# BoB_Brain_v03.net
KiCad netlist of a schematic drawn in EAGLE
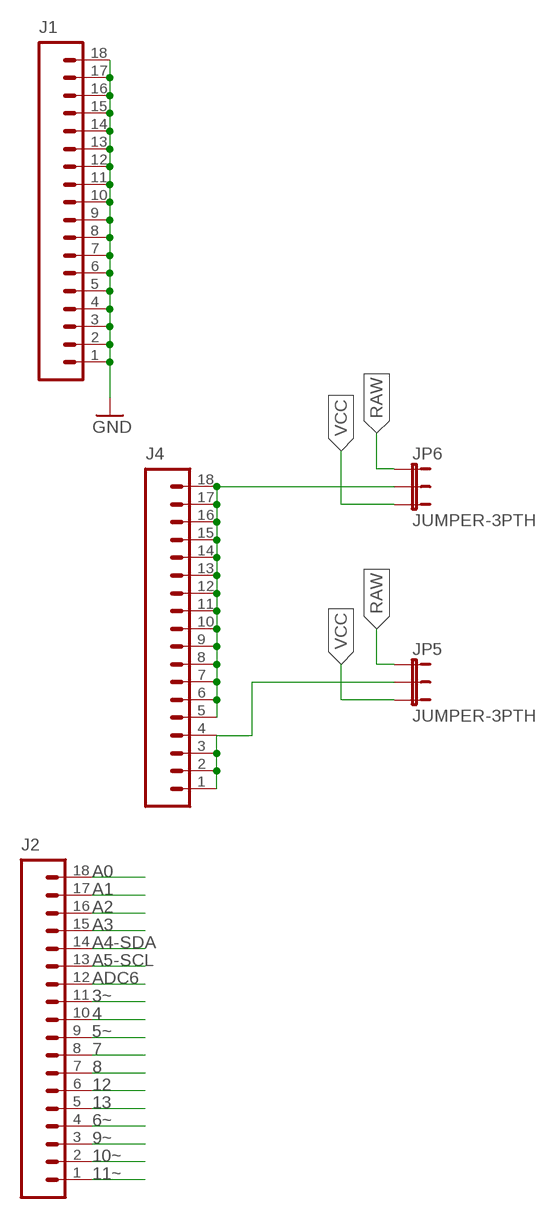
[diagram p0: schematic, sheet 1]
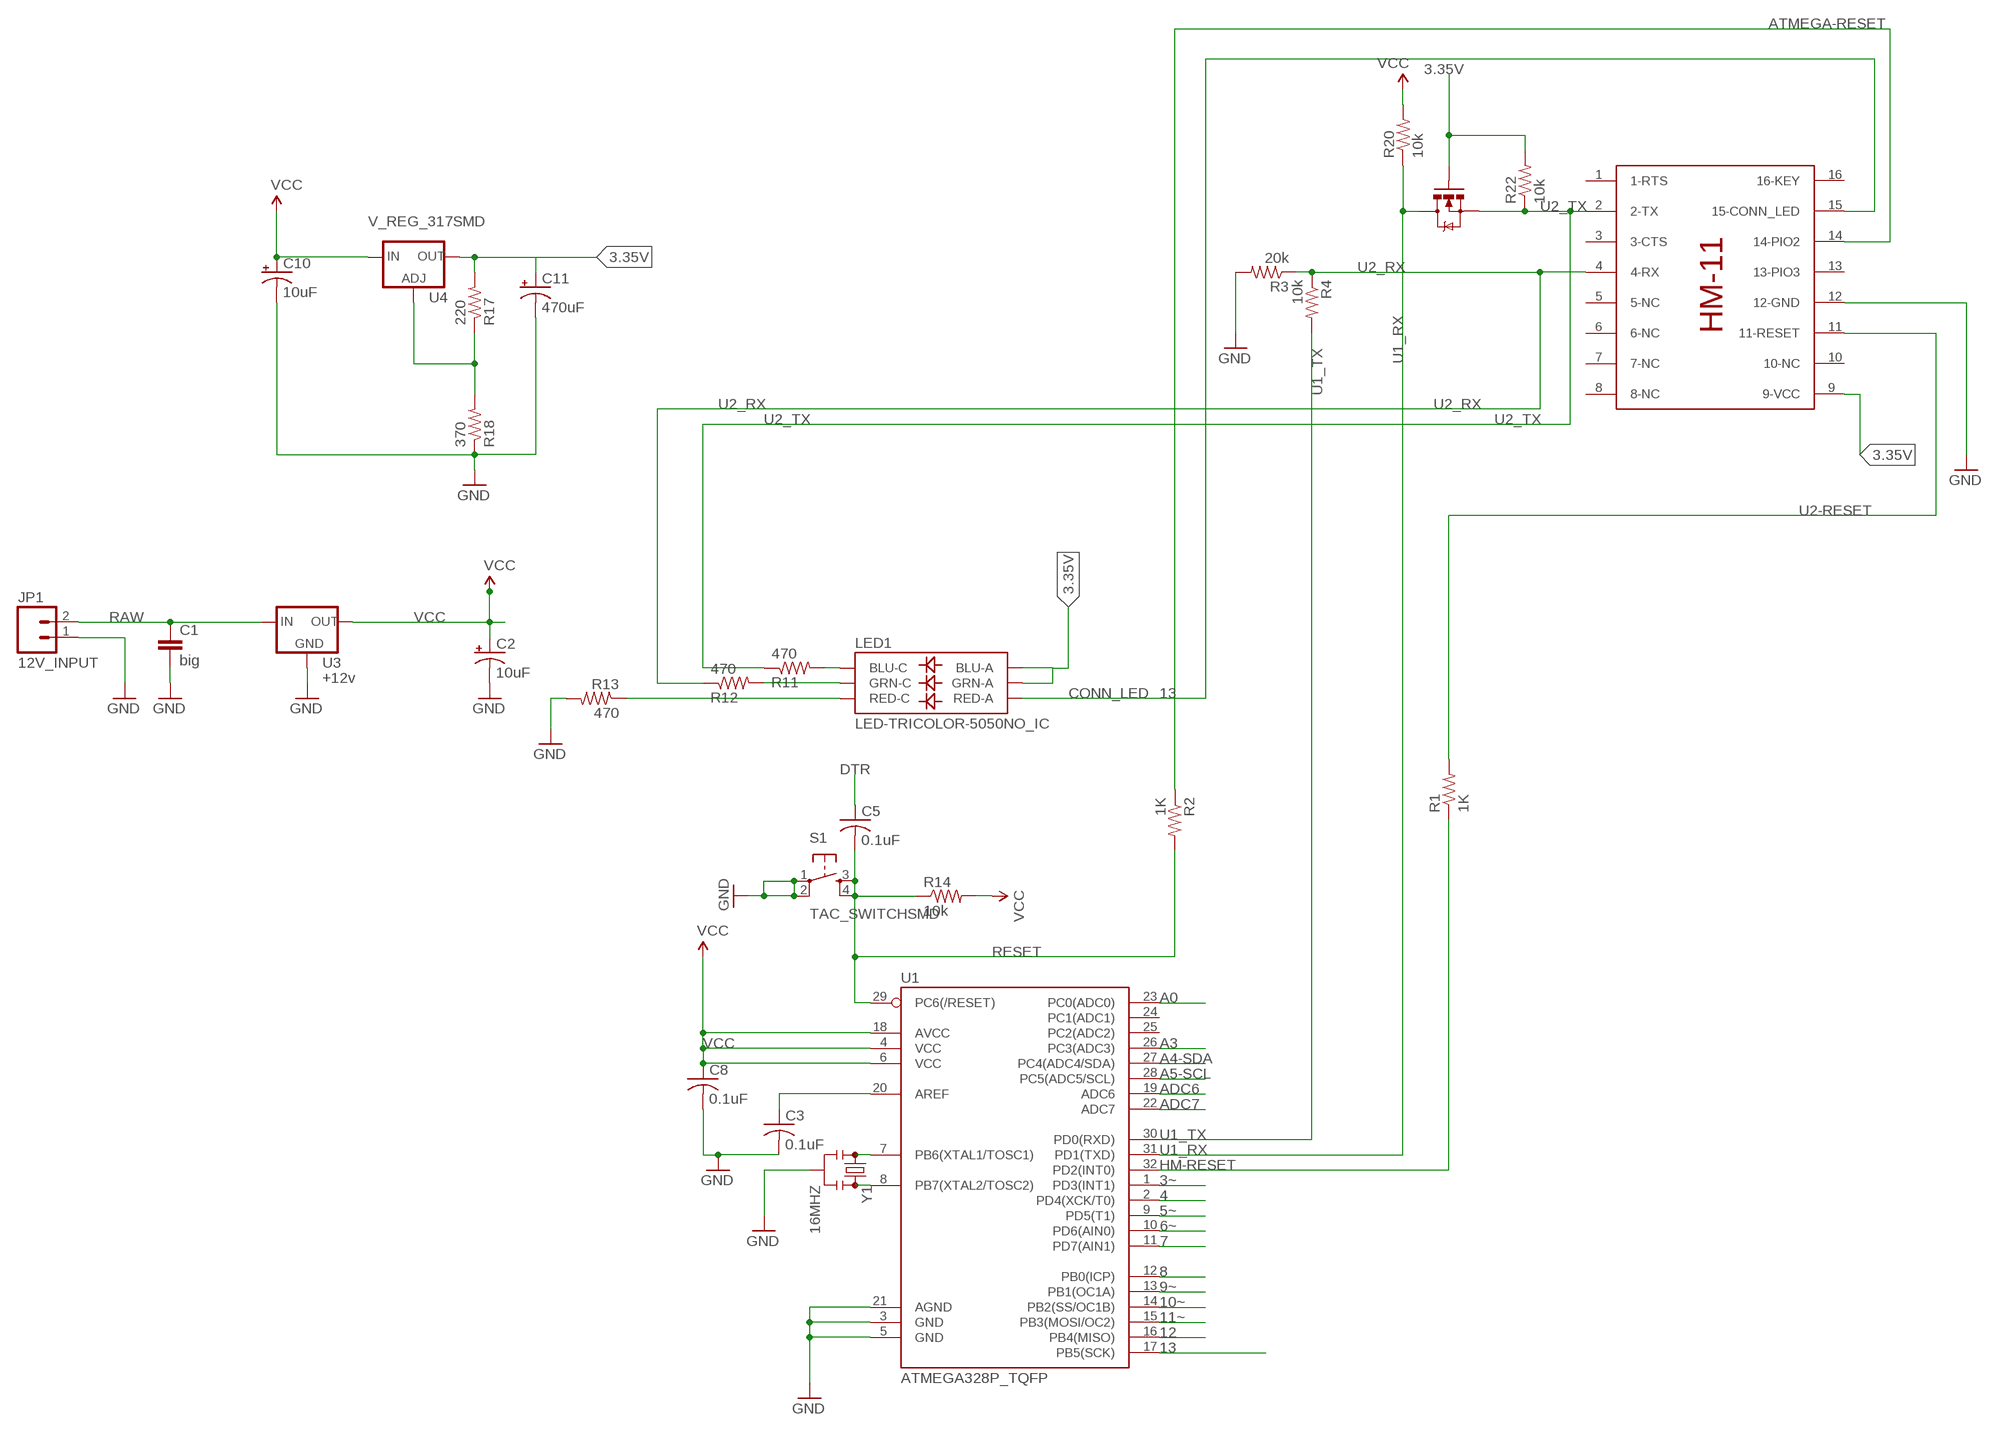
[diagram p1: schematic, sheet 2]

(export (version "E")
  (design (tool "Eeschema 10.0.6"))
  (components
    (comp (ref "C1")
      (value "big")
      (footprint "eagle-import:CAP-PTH-5MM")
      (libsource (lib "eagle-import") (part "CAPPTH1"))
    )
    (comp (ref "C2")
      (value "10uF")
      (footprint "eagle-import:EIA3528")
      (libsource (lib "eagle-import") (part "CAP_POL3528"))
    )
    (comp (ref "C3")
      (value "0.1uF")
      (footprint "eagle-import:C0402")
      (libsource (lib "eagle-import") (part "C-USC0402"))
    )
    (comp (ref "C5")
      (value "0.1uF")
      (footprint "eagle-import:C0805K")
      (libsource (lib "eagle-import") (part "C-USC0805K"))
    )
    (comp (ref "C8")
      (value "0.1uF")
      (footprint "eagle-import:C0402")
      (libsource (lib "eagle-import") (part "C-USC0402"))
    )
    (comp (ref "C10")
      (value "10uF")
      (footprint "eagle-import:EIA3528")
      (libsource (lib "eagle-import") (part "CAP_POL3528"))
    )
    (comp (ref "C11")
      (value "470uF")
      (footprint "eagle-import:D_7343-31W")
      (libsource (lib "eagle-import") (part "CPOL-USD/7343-31W"))
    )
    (comp (ref "JP1")
      (value "12V_INPUT")
      (footprint "eagle-import:SCREWTERMINAL-5MM-2")
      (libsource (lib "eagle-import") (part "M025MM"))
    )
    (comp (ref "LED1")
      (value "LED-TRICOLOR-5050NO_IC")
      (footprint "eagle-import:LED-TRICOLOR-5050")
      (libsource (lib "eagle-import") (part "LED-TRICOLOR-5050NO_IC"))
    )
    (comp (ref "Q1")
      (value "MOSFET-NCHANNELAO3404A")
      (footprint "eagle-import:SOT23-3")
      (libsource (lib "eagle-import") (part "MOSFET-NCHANNELAO3404A"))
    )
    (comp (ref "R1")
      (value "1K")
      (footprint "eagle-import:R0805W")
      (libsource (lib "eagle-import") (part "R-US_R0805W"))
    )
    (comp (ref "R2")
      (value "1K")
      (footprint "eagle-import:R0805W")
      (libsource (lib "eagle-import") (part "R-US_R0805W"))
    )
    (comp (ref "R3")
      (value "20k")
      (footprint "eagle-import:R0805W")
      (libsource (lib "eagle-import") (part "R-US_R0805W"))
    )
    (comp (ref "R4")
      (value "10k")
      (footprint "eagle-import:R0805W")
      (libsource (lib "eagle-import") (part "R-US_R0805W"))
    )
    (comp (ref "R11")
      (value "470")
      (footprint "eagle-import:R0805W")
      (libsource (lib "eagle-import") (part "R-US_R0805W"))
    )
    (comp (ref "R12")
      (value "470")
      (footprint "eagle-import:R0805W")
      (libsource (lib "eagle-import") (part "R-US_R0805W"))
    )
    (comp (ref "R13")
      (value "470")
      (footprint "eagle-import:R0805W")
      (libsource (lib "eagle-import") (part "R-US_R0805W"))
    )
    (comp (ref "R14")
      (value "10k")
      (footprint "eagle-import:R0805W")
      (libsource (lib "eagle-import") (part "R-US_R0805W"))
    )
    (comp (ref "R17")
      (value "220")
      (footprint "eagle-import:R0805W")
      (libsource (lib "eagle-import") (part "R-US_R0805W"))
    )
    (comp (ref "R18")
      (value "370")
      (footprint "eagle-import:R0805W")
      (libsource (lib "eagle-import") (part "R-US_R0805W"))
    )
    (comp (ref "R20")
      (value "10k")
      (footprint "eagle-import:R0805W")
      (libsource (lib "eagle-import") (part "R-US_R0805W"))
    )
    (comp (ref "R22")
      (value "10k")
      (footprint "eagle-import:R0805W")
      (libsource (lib "eagle-import") (part "R-US_R0805W"))
    )
    (comp (ref "S1")
      (value "TAC_SWITCHSMD")
      (footprint "eagle-import:TACTILE-SWITCH-SMD")
      (libsource (lib "eagle-import") (part "TAC_SWITCHSMD"))
    )
    (comp (ref "U$1")
      (value "HM-11")
      (footprint "eagle-import:HM-11")
      (libsource (lib "eagle-import") (part "HM-11"))
    )
    (comp (ref "U1")
      (value "ATMEGA328P_TQFP")
      (footprint "eagle-import:TQFP32-08")
      (libsource (lib "eagle-import") (part "ATMEGA328P_TQFP"))
    )
    (comp (ref "U3")
      (value "+12v")
      (footprint "eagle-import:TO-252")
      (libsource (lib "eagle-import") (part "V_REG_78XX7812"))
    )
    (comp (ref "U4")
      (value "V_REG_317SMD")
      (footprint "eagle-import:SOT223")
      (libsource (lib "eagle-import") (part "V_REG_317SMD"))
    )
    (comp (ref "Y1")
      (value "16MHZ")
      (footprint "eagle-import:RESONATOR-SMD")
      (libsource (lib "eagle-import") (part "RESONATOR16MHZ"))
    )
    (comp (ref "J1")
      (value "M18_")
      (footprint "eagle-import:1X18")
      (libsource (lib "eagle-import") (part "M18_"))
    )
    (comp (ref "J2")
      (value "M18_")
      (footprint "eagle-import:1X18")
      (libsource (lib "eagle-import") (part "M18_"))
    )
    (comp (ref "J4")
      (value "M18_")
      (footprint "eagle-import:1X18")
      (libsource (lib "eagle-import") (part "M18_"))
    )
    (comp (ref "JP5")
      (value "JUMPER-3PTH")
      (footprint "eagle-import:1X03")
      (libsource (lib "eagle-import") (part "JUMPER-3PTH"))
    )
    (comp (ref "JP6")
      (value "JUMPER-3PTH")
      (footprint "eagle-import:1X03")
      (libsource (lib "eagle-import") (part "JUMPER-3PTH"))
    )
  )
  (nets
    (net (code "1") (name "3.35V") (class "Default")
      (node (ref "C11") (pin "+") (pinfunction "+_+") (pintype "passive"))
      (node (ref "LED1") (pin "1") (pinfunction "GRN-A_1") (pintype "bidirectional"))
      (node (ref "LED1") (pin "3") (pinfunction "BLU-A_3") (pintype "bidirectional"))
      (node (ref "Q1") (pin "1") (pinfunction "G_1") (pintype "passive"))
      (node (ref "R17") (pin "2") (pinfunction "2_2") (pintype "passive"))
      (node (ref "R22") (pin "2") (pinfunction "2_2") (pintype "passive"))
      (node (ref "U$1") (pin "9") (pinfunction "9-VCC_9") (pintype "bidirectional"))
      (node (ref "U4") (pin "2") (pinfunction "OUT_2") (pintype "output"))
    )
    (net (code "2") (name "3~{}") (class "Default")
      (node (ref "J2") (pin "18") (pinfunction "18_18") (pintype "passive"))
      (node (ref "U1") (pin "1") (pinfunction "PD3(INT1)_1") (pintype "bidirectional"))
    )
    (net (code "3") (name "4") (class "Default")
      (node (ref "J2") (pin "17") (pinfunction "17_17") (pintype "passive"))
      (node (ref "U1") (pin "2") (pinfunction "PD4(XCK/T0)_2") (pintype "bidirectional"))
    )
    (net (code "4") (name "5~{}") (class "Default")
      (node (ref "J2") (pin "9") (pinfunction "9_9") (pintype "passive"))
      (node (ref "U1") (pin "9") (pinfunction "PD5(T1)_9") (pintype "bidirectional"))
    )
    (net (code "5") (name "6~{}") (class "Default")
      (node (ref "J2") (pin "4") (pinfunction "4_4") (pintype "passive"))
      (node (ref "U1") (pin "10") (pinfunction "PD6(AIN0)_10") (pintype "bidirectional"))
    )
    (net (code "6") (name "7") (class "Default")
      (node (ref "J2") (pin "8") (pinfunction "8_8") (pintype "passive"))
      (node (ref "U1") (pin "11") (pinfunction "PD7(AIN1)_11") (pintype "bidirectional"))
    )
    (net (code "7") (name "8") (class "Default")
      (node (ref "J2") (pin "7") (pinfunction "7_7") (pintype "passive"))
      (node (ref "U1") (pin "12") (pinfunction "PB0(ICP)_12") (pintype "bidirectional"))
    )
    (net (code "8") (name "9~{}") (class "Default")
      (node (ref "J2") (pin "3") (pinfunction "3_3") (pintype "passive"))
      (node (ref "U1") (pin "13") (pinfunction "PB1(OC1A)_13") (pintype "bidirectional"))
    )
    (net (code "9") (name "10~{}") (class "Default")
      (node (ref "J2") (pin "2") (pinfunction "2_2") (pintype "passive"))
      (node (ref "U1") (pin "14") (pinfunction "PB2(SS/OC1B)_14") (pintype "bidirectional"))
    )
    (net (code "10") (name "11~{}") (class "Default")
      (node (ref "J2") (pin "1") (pinfunction "1_1") (pintype "passive"))
      (node (ref "U1") (pin "15") (pinfunction "PB3(MOSI/OC2)_15") (pintype "bidirectional"))
    )
    (net (code "11") (name "12") (class "Default")
      (node (ref "J2") (pin "6") (pinfunction "6_6") (pintype "passive"))
      (node (ref "U1") (pin "16") (pinfunction "PB4(MISO)_16") (pintype "bidirectional"))
    )
    (net (code "12") (name "13") (class "Default")
      (node (ref "J2") (pin "5") (pinfunction "5_5") (pintype "passive"))
      (node (ref "U1") (pin "17") (pinfunction "PB5(SCK)_17") (pintype "bidirectional"))
    )
    (net (code "13") (name "A0") (class "Default")
      (node (ref "J2") (pin "12") (pinfunction "12_12") (pintype "passive"))
      (node (ref "U1") (pin "23") (pinfunction "PC0(ADC0)_23") (pintype "bidirectional"))
    )
    (net (code "14") (name "A1") (class "Default")
      (node (ref "J2") (pin "10") (pinfunction "10_10") (pintype "passive"))
    )
    (net (code "15") (name "A2") (class "Default")
      (node (ref "J2") (pin "16") (pinfunction "16_16") (pintype "passive"))
    )
    (net (code "16") (name "A3") (class "Default")
      (node (ref "J2") (pin "15") (pinfunction "15_15") (pintype "passive"))
      (node (ref "U1") (pin "26") (pinfunction "PC3(ADC3)_26") (pintype "bidirectional"))
    )
    (net (code "17") (name "A4-SDA") (class "Default")
      (node (ref "J2") (pin "14") (pinfunction "14_14") (pintype "passive"))
      (node (ref "U1") (pin "27") (pinfunction "PC4(ADC4/SDA)_27") (pintype "bidirectional"))
    )
    (net (code "18") (name "A5-SCL") (class "Default")
      (node (ref "J2") (pin "13") (pinfunction "13_13") (pintype "passive"))
      (node (ref "U1") (pin "28") (pinfunction "PC5(ADC5/SCL)_28") (pintype "bidirectional"))
    )
    (net (code "19") (name "ADC6") (class "Default")
      (node (ref "J2") (pin "11") (pinfunction "11_11") (pintype "passive"))
      (node (ref "U1") (pin "19") (pinfunction "ADC6_19") (pintype "bidirectional"))
    )
    (net (code "20") (name "ADC7") (class "Default")
      (node (ref "U1") (pin "22") (pinfunction "ADC7_22") (pintype "bidirectional"))
    )
    (net (code "21") (name "ATMEGA-RESET") (class "Default")
      (node (ref "R2") (pin "1") (pinfunction "1_1") (pintype "passive"))
      (node (ref "U$1") (pin "14") (pinfunction "14-PIO2_14") (pintype "bidirectional"))
    )
    (net (code "22") (name "CONN_LED") (class "Default")
      (node (ref "LED1") (pin "2") (pinfunction "RED-A_2") (pintype "bidirectional"))
      (node (ref "U$1") (pin "15") (pinfunction "15-CONN_LED_15") (pintype "bidirectional"))
    )
    (net (code "23") (name "DTR") (class "Default")
      (node (ref "C5") (pin "1") (pinfunction "1_1") (pintype "passive"))
    )
    (net (code "24") (name "GND") (class "Default")
      (node (ref "C1") (pin "2") (pinfunction "2_2") (pintype "passive"))
      (node (ref "C10") (pin "C") (pinfunction "-_C") (pintype "passive"))
      (node (ref "C11") (pin "-") (pinfunction "-_-") (pintype "passive"))
      (node (ref "C2") (pin "C") (pinfunction "-_C") (pintype "passive"))
      (node (ref "C3") (pin "2") (pinfunction "2_2") (pintype "passive"))
      (node (ref "C8") (pin "2") (pinfunction "2_2") (pintype "passive"))
      (node (ref "J1") (pin "1") (pinfunction "1_1") (pintype "passive"))
      (node (ref "J1") (pin "10") (pinfunction "10_10") (pintype "passive"))
      (node (ref "J1") (pin "11") (pinfunction "11_11") (pintype "passive"))
      (node (ref "J1") (pin "12") (pinfunction "12_12") (pintype "passive"))
      (node (ref "J1") (pin "13") (pinfunction "13_13") (pintype "passive"))
      (node (ref "J1") (pin "14") (pinfunction "14_14") (pintype "passive"))
      (node (ref "J1") (pin "15") (pinfunction "15_15") (pintype "passive"))
      (node (ref "J1") (pin "16") (pinfunction "16_16") (pintype "passive"))
      (node (ref "J1") (pin "17") (pinfunction "17_17") (pintype "passive"))
      (node (ref "J1") (pin "18") (pinfunction "18_18") (pintype "passive"))
      (node (ref "J1") (pin "2") (pinfunction "2_2") (pintype "passive"))
      (node (ref "J1") (pin "3") (pinfunction "3_3") (pintype "passive"))
      (node (ref "J1") (pin "4") (pinfunction "4_4") (pintype "passive"))
      (node (ref "J1") (pin "5") (pinfunction "5_5") (pintype "passive"))
      (node (ref "J1") (pin "6") (pinfunction "6_6") (pintype "passive"))
      (node (ref "J1") (pin "7") (pinfunction "7_7") (pintype "passive"))
      (node (ref "J1") (pin "8") (pinfunction "8_8") (pintype "passive"))
      (node (ref "J1") (pin "9") (pinfunction "9_9") (pintype "passive"))
      (node (ref "JP1") (pin "1") (pinfunction "1_1") (pintype "passive"))
      (node (ref "R13") (pin "2") (pinfunction "2_2") (pintype "passive"))
      (node (ref "R18") (pin "1") (pinfunction "1_1") (pintype "passive"))
      (node (ref "R3") (pin "2") (pinfunction "2_2") (pintype "passive"))
      (node (ref "S1") (pin "1") (pinfunction "1_1") (pintype "passive"))
      (node (ref "S1") (pin "2") (pinfunction "2_2") (pintype "passive"))
      (node (ref "U$1") (pin "12") (pinfunction "12-GND_12") (pintype "bidirectional"))
      (node (ref "U1") (pin "21") (pinfunction "AGND_21") (pintype "bidirectional"))
      (node (ref "U1") (pin "3") (pinfunction "GND_3") (pintype "bidirectional"))
      (node (ref "U1") (pin "5") (pinfunction "GND_5") (pintype "bidirectional"))
      (node (ref "U3") (pin "3") (pinfunction "GND_3") (pintype "input"))
      (node (ref "Y1") (pin "2") (pinfunction "2_2") (pintype "passive"))
    )
    (net (code "25") (name "HM-RESET") (class "Default")
      (node (ref "R1") (pin "1") (pinfunction "1_1") (pintype "passive"))
      (node (ref "U1") (pin "32") (pinfunction "PD2(INT0)_32") (pintype "bidirectional"))
    )
    (net (code "26") (name "Net-(J4-Pad1)") (class "Default")
      (node (ref "J4") (pin "1") (pinfunction "1_1") (pintype "passive"))
      (node (ref "J4") (pin "2") (pinfunction "2_2") (pintype "passive"))
      (node (ref "J4") (pin "3") (pinfunction "3_3") (pintype "passive"))
      (node (ref "J4") (pin "4") (pinfunction "4_4") (pintype "passive"))
      (node (ref "JP5") (pin "2") (pinfunction "2_2") (pintype "passive"))
    )
    (net (code "27") (name "Net-(J4-Pad10)") (class "Default")
      (node (ref "J4") (pin "10") (pinfunction "10_10") (pintype "passive"))
      (node (ref "J4") (pin "11") (pinfunction "11_11") (pintype "passive"))
      (node (ref "J4") (pin "12") (pinfunction "12_12") (pintype "passive"))
      (node (ref "J4") (pin "13") (pinfunction "13_13") (pintype "passive"))
      (node (ref "J4") (pin "14") (pinfunction "14_14") (pintype "passive"))
      (node (ref "J4") (pin "15") (pinfunction "15_15") (pintype "passive"))
      (node (ref "J4") (pin "16") (pinfunction "16_16") (pintype "passive"))
      (node (ref "J4") (pin "17") (pinfunction "17_17") (pintype "passive"))
      (node (ref "J4") (pin "18") (pinfunction "18_18") (pintype "passive"))
      (node (ref "J4") (pin "5") (pinfunction "5_5") (pintype "passive"))
      (node (ref "J4") (pin "6") (pinfunction "6_6") (pintype "passive"))
      (node (ref "J4") (pin "7") (pinfunction "7_7") (pintype "passive"))
      (node (ref "J4") (pin "8") (pinfunction "8_8") (pintype "passive"))
      (node (ref "J4") (pin "9") (pinfunction "9_9") (pintype "passive"))
      (node (ref "JP6") (pin "2") (pinfunction "2_2") (pintype "passive"))
    )
    (net (code "28") (name "Net-(LED1-BLU-C)") (class "Default")
      (node (ref "LED1") (pin "4") (pinfunction "BLU-C_4") (pintype "bidirectional"))
      (node (ref "R11") (pin "2") (pinfunction "2_2") (pintype "passive"))
    )
    (net (code "29") (name "Net-(LED1-GRN-C)") (class "Default")
      (node (ref "LED1") (pin "6") (pinfunction "GRN-C_6") (pintype "bidirectional"))
      (node (ref "R12") (pin "2") (pinfunction "2_2") (pintype "passive"))
    )
    (net (code "30") (name "Net-(LED1-RED-C)") (class "Default")
      (node (ref "LED1") (pin "5") (pinfunction "RED-C_5") (pintype "bidirectional"))
      (node (ref "R13") (pin "1") (pinfunction "1_1") (pintype "passive"))
    )
    (net (code "31") (name "Net-(U1-AREF)") (class "Default")
      (node (ref "C3") (pin "1") (pinfunction "1_1") (pintype "passive"))
      (node (ref "U1") (pin "20") (pinfunction "AREF_20") (pintype "bidirectional"))
    )
    (net (code "32") (name "Net-(U1-PB6(XTAL1{slash}TOSC1))") (class "Default")
      (node (ref "U1") (pin "7") (pinfunction "PB6(XTAL1/TOSC1)_7") (pintype "bidirectional"))
      (node (ref "Y1") (pin "1") (pinfunction "1_1") (pintype "passive"))
    )
    (net (code "33") (name "Net-(U1-PB7(XTAL2{slash}TOSC2))") (class "Default")
      (node (ref "U1") (pin "8") (pinfunction "PB7(XTAL2/TOSC2)_8") (pintype "bidirectional"))
      (node (ref "Y1") (pin "3") (pinfunction "3_3") (pintype "passive"))
    )
    (net (code "34") (name "Net-(U4-ADJ)") (class "Default")
      (node (ref "R17") (pin "1") (pinfunction "1_1") (pintype "passive"))
      (node (ref "R18") (pin "2") (pinfunction "2_2") (pintype "passive"))
      (node (ref "U4") (pin "1") (pinfunction "ADJ_1") (pintype "input"))
    )
    (net (code "35") (name "RAW") (class "Default")
      (node (ref "C1") (pin "1") (pinfunction "1_1") (pintype "passive"))
      (node (ref "JP1") (pin "2") (pinfunction "2_2") (pintype "passive"))
      (node (ref "JP5") (pin "1") (pinfunction "1_1") (pintype "passive"))
      (node (ref "JP6") (pin "1") (pinfunction "1_1") (pintype "passive"))
      (node (ref "U3") (pin "1") (pinfunction "IN_1") (pintype "input"))
    )
    (net (code "36") (name "RESET") (class "Default")
      (node (ref "C5") (pin "2") (pinfunction "2_2") (pintype "passive"))
      (node (ref "R14") (pin "1") (pinfunction "1_1") (pintype "passive"))
      (node (ref "R2") (pin "2") (pinfunction "2_2") (pintype "passive"))
      (node (ref "S1") (pin "3") (pinfunction "3_3") (pintype "passive"))
      (node (ref "S1") (pin "4") (pinfunction "4_4") (pintype "passive"))
      (node (ref "U1") (pin "29") (pinfunction "PC6(/RESET)_29") (pintype "bidirectional"))
    )
    (net (code "37") (name "U1_RX") (class "Default")
      (node (ref "Q1") (pin "3") (pinfunction "D_3") (pintype "passive"))
      (node (ref "R20") (pin "1") (pinfunction "1_1") (pintype "passive"))
      (node (ref "U1") (pin "31") (pinfunction "PD1(TXD)_31") (pintype "bidirectional"))
    )
    (net (code "38") (name "U1_TX") (class "Default")
      (node (ref "R4") (pin "2") (pinfunction "2_2") (pintype "passive"))
      (node (ref "U1") (pin "30") (pinfunction "PD0(RXD)_30") (pintype "bidirectional"))
    )
    (net (code "39") (name "U2-RESET") (class "Default")
      (node (ref "R1") (pin "2") (pinfunction "2_2") (pintype "passive"))
      (node (ref "U$1") (pin "11") (pinfunction "11-RESET_11") (pintype "bidirectional"))
    )
    (net (code "40") (name "U2_RX") (class "Default")
      (node (ref "R12") (pin "1") (pinfunction "1_1") (pintype "passive"))
      (node (ref "R3") (pin "1") (pinfunction "1_1") (pintype "passive"))
      (node (ref "R4") (pin "1") (pinfunction "1_1") (pintype "passive"))
      (node (ref "U$1") (pin "4") (pinfunction "4-RX_4") (pintype "bidirectional"))
    )
    (net (code "41") (name "U2_TX") (class "Default")
      (node (ref "Q1") (pin "2") (pinfunction "S_2") (pintype "passive"))
      (node (ref "R11") (pin "1") (pinfunction "1_1") (pintype "passive"))
      (node (ref "R22") (pin "1") (pinfunction "1_1") (pintype "passive"))
      (node (ref "U$1") (pin "2") (pinfunction "2-TX_2") (pintype "bidirectional"))
    )
    (net (code "42") (name "VCC") (class "Default")
      (node (ref "C10") (pin "A") (pinfunction "+_A") (pintype "passive"))
      (node (ref "C2") (pin "A") (pinfunction "+_A") (pintype "passive"))
      (node (ref "C8") (pin "1") (pinfunction "1_1") (pintype "passive"))
      (node (ref "JP5") (pin "3") (pinfunction "3_3") (pintype "passive"))
      (node (ref "JP6") (pin "3") (pinfunction "3_3") (pintype "passive"))
      (node (ref "R14") (pin "2") (pinfunction "2_2") (pintype "passive"))
      (node (ref "R20") (pin "2") (pinfunction "2_2") (pintype "passive"))
      (node (ref "U1") (pin "18") (pinfunction "AVCC_18") (pintype "bidirectional"))
      (node (ref "U1") (pin "4") (pinfunction "VCC_4") (pintype "bidirectional"))
      (node (ref "U1") (pin "6") (pinfunction "VCC_6") (pintype "bidirectional"))
      (node (ref "U3") (pin "2") (pinfunction "OUT_2") (pintype "passive"))
      (node (ref "U4") (pin "3") (pinfunction "IN_3") (pintype "input"))
    )
    (net (code "43") (name "unconnected-(U$1-1-RTS-Pad1)") (class "Default")
      (node (ref "U$1") (pin "1") (pinfunction "1-RTS_1") (pintype "bidirectional"))
    )
    (net (code "44") (name "unconnected-(U$1-3-CTS-Pad3)") (class "Default")
      (node (ref "U$1") (pin "3") (pinfunction "3-CTS_3") (pintype "bidirectional"))
    )
    (net (code "45") (name "unconnected-(U$1-5-NC-Pad5)") (class "Default")
      (node (ref "U$1") (pin "5") (pinfunction "5-NC_5") (pintype "bidirectional"))
    )
    (net (code "46") (name "unconnected-(U$1-6-NC-Pad6)") (class "Default")
      (node (ref "U$1") (pin "6") (pinfunction "6-NC_6") (pintype "bidirectional"))
    )
    (net (code "47") (name "unconnected-(U$1-7-NC-Pad7)") (class "Default")
      (node (ref "U$1") (pin "7") (pinfunction "7-NC_7") (pintype "bidirectional"))
    )
    (net (code "48") (name "unconnected-(U$1-8-NC-Pad8)") (class "Default")
      (node (ref "U$1") (pin "8") (pinfunction "8-NC_8") (pintype "bidirectional"))
    )
    (net (code "49") (name "unconnected-(U$1-10-NC-Pad10)") (class "Default")
      (node (ref "U$1") (pin "10") (pinfunction "10-NC_10") (pintype "bidirectional"))
    )
    (net (code "50") (name "unconnected-(U$1-13-PIO3-Pad13)") (class "Default")
      (node (ref "U$1") (pin "13") (pinfunction "13-PIO3_13") (pintype "bidirectional"))
    )
    (net (code "51") (name "unconnected-(U$1-16-KEY-Pad16)") (class "Default")
      (node (ref "U$1") (pin "16") (pinfunction "16-KEY_16") (pintype "bidirectional"))
    )
    (net (code "52") (name "unconnected-(U1-PC1(ADC1)-Pad24)") (class "Default")
      (node (ref "U1") (pin "24") (pinfunction "PC1(ADC1)_24") (pintype "bidirectional"))
    )
    (net (code "53") (name "unconnected-(U1-PC2(ADC2)-Pad25)") (class "Default")
      (node (ref "U1") (pin "25") (pinfunction "PC2(ADC2)_25") (pintype "bidirectional"))
    )
  )
)
